# Arduino_MEGA2560_ref.net
KiCad netlist of a schematic drawn in EAGLE
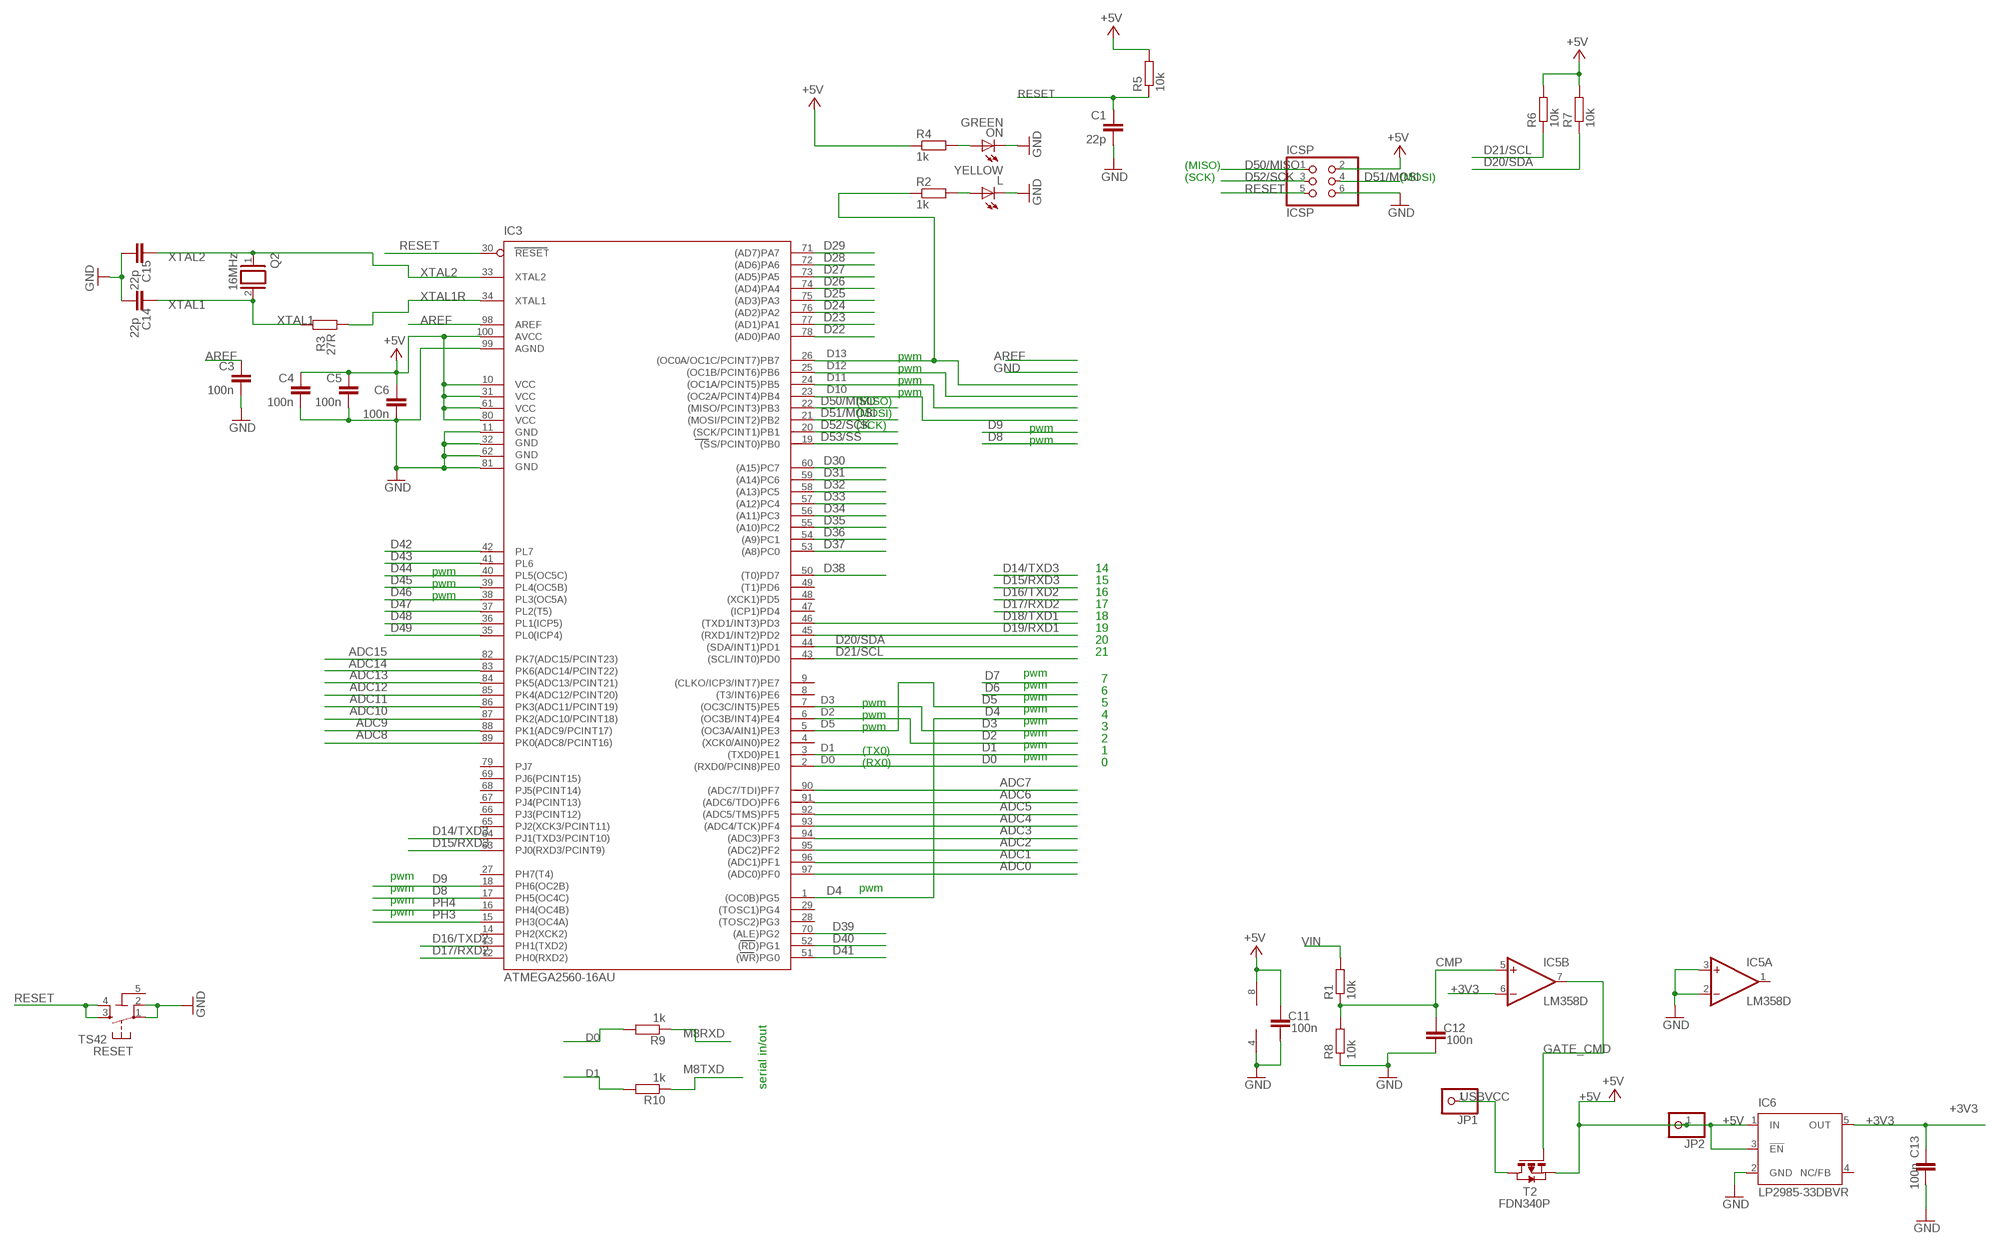
[diagram p0: schematic, sheet 1]

(export (version "E")
  (design (tool "Eeschema 10.0.6"))
  (components
    (comp (ref "C1")
      (value "22p")
      (footprint "eagle-import:C0603-ROUND")
      (libsource (lib "eagle-import") (part "C-EU0603-RND"))
    )
    (comp (ref "C3")
      (value "100n")
      (footprint "eagle-import:C0603-ROUND")
      (libsource (lib "eagle-import") (part "C-EU0603-RND"))
    )
    (comp (ref "C4")
      (value "100n")
      (footprint "eagle-import:C0603-ROUND")
      (libsource (lib "eagle-import") (part "C-EU0603-RND"))
    )
    (comp (ref "C5")
      (value "100n")
      (footprint "eagle-import:C0603-ROUND")
      (libsource (lib "eagle-import") (part "C-EU0603-RND"))
    )
    (comp (ref "C6")
      (value "100n")
      (footprint "eagle-import:C0603-ROUND")
      (libsource (lib "eagle-import") (part "C-EU0603-RND"))
    )
    (comp (ref "C11")
      (value "100n")
      (footprint "eagle-import:C0603")
      (libsource (lib "eagle-import") (part "rcl_C-EUC0603"))
    )
    (comp (ref "C12")
      (value "100n")
      (footprint "eagle-import:C0603-ROUND")
      (libsource (lib "eagle-import") (part "C-EU0603-RND"))
    )
    (comp (ref "C13")
      (value "100n")
      (footprint "eagle-import:C0603-ROUND")
      (libsource (lib "eagle-import") (part "C-EU0603-RND"))
    )
    (comp (ref "C14")
      (value "22p")
      (footprint "eagle-import:C0603-ROUND")
      (libsource (lib "eagle-import") (part "C-EU0603-RND"))
    )
    (comp (ref "C15")
      (value "22p")
      (footprint "eagle-import:C0603-ROUND")
      (libsource (lib "eagle-import") (part "C-EU0603-RND"))
    )
    (comp (ref "IC3")
      (value "ATMEGA2560-16AU")
      (footprint "eagle-import:TQFP100")
      (libsource (lib "eagle-import") (part "ATMEGAAU1280-16"))
    )
    (comp (ref "IC5")
      (value "LM358D")
      (footprint "eagle-import:SO08")
      (libsource (lib "eagle-import") (part "LM358D"))
    )
    (comp (ref "IC6")
      (value "LP2985-33DBVR")
      (footprint "eagle-import:SOT23-DBV")
      (libsource (lib "eagle-import") (part "TPS77033"))
    )
    (comp (ref "ICSP")
      (value "ICSP")
      (footprint "eagle-import:2X03")
      (libsource (lib "eagle-import") (part "PINHD-2X3"))
    )
    (comp (ref "JP1")
      (value "PINHD-1X1")
      (footprint "eagle-import:1X01")
      (libsource (lib "eagle-import") (part "PINHD-1X1"))
    )
    (comp (ref "JP2")
      (value "PINHD-1X1")
      (footprint "eagle-import:1X01")
      (libsource (lib "eagle-import") (part "PINHD-1X1"))
    )
    (comp (ref "L")
      (value "YELLOW")
      (footprint "eagle-import:CHIP-LED0805")
      (libsource (lib "eagle-import") (part "LEDCHIP-LED0805"))
    )
    (comp (ref "ON")
      (value "GREEN")
      (footprint "eagle-import:CHIP-LED0805")
      (libsource (lib "eagle-import") (part "LEDCHIP-LED0805"))
    )
    (comp (ref "Q2")
      (value "16MHz")
      (footprint "eagle-import:QS")
      (libsource (lib "eagle-import") (part "XTAL/S"))
    )
    (comp (ref "R1")
      (value "10k")
      (footprint "eagle-import:R0603")
      (libsource (lib "eagle-import") (part "rcl_334_R-EU_R0603"))
    )
    (comp (ref "R2")
      (value "1k")
      (footprint "eagle-import:R0603")
      (libsource (lib "eagle-import") (part "rcl_334_R-EU_R0603"))
    )
    (comp (ref "R3")
      (value "27R")
      (footprint "eagle-import:R0603-ROUND")
      (libsource (lib "eagle-import") (part "R-EU_R0603"))
    )
    (comp (ref "R4")
      (value "1k")
      (footprint "eagle-import:R0603")
      (libsource (lib "eagle-import") (part "rcl_334_R-EU_R0603"))
    )
    (comp (ref "R5")
      (value "10k")
      (footprint "eagle-import:R0603")
      (libsource (lib "eagle-import") (part "rcl_334_R-EU_R0603"))
    )
    (comp (ref "R6")
      (value "10k")
      (footprint "eagle-import:R0603")
      (libsource (lib "eagle-import") (part "rcl_334_R-EU_R0603"))
    )
    (comp (ref "R7")
      (value "10k")
      (footprint "eagle-import:R0603")
      (libsource (lib "eagle-import") (part "rcl_334_R-EU_R0603"))
    )
    (comp (ref "R8")
      (value "10k")
      (footprint "eagle-import:R0603")
      (libsource (lib "eagle-import") (part "rcl_334_R-EU_R0603"))
    )
    (comp (ref "R9")
      (value "1k")
      (footprint "eagle-import:R0603")
      (libsource (lib "eagle-import") (part "rcl_334_R-EU_R0603"))
    )
    (comp (ref "R10")
      (value "1k")
      (footprint "eagle-import:R0603")
      (libsource (lib "eagle-import") (part "rcl_334_R-EU_R0603"))
    )
    (comp (ref "RESET")
      (value "TS42")
      (footprint "eagle-import:TS42")
      (libsource (lib "eagle-import") (part "TS42"))
    )
    (comp (ref "T2")
      (value "FDN340P")
      (footprint "eagle-import:SOT-23")
      (libsource (lib "eagle-import") (part "PMOSSOT23"))
    )
  )
  (nets
    (net (code "1") (name "+5V") (class "Default")
      (node (ref "C11") (pin "2") (pinfunction "2_2") (pintype "passive"))
      (node (ref "C4") (pin "1") (pinfunction "1_1") (pintype "passive"))
      (node (ref "C5") (pin "1") (pinfunction "1_1") (pintype "passive"))
      (node (ref "C6") (pin "1") (pinfunction "1_1") (pintype "passive"))
      (node (ref "IC3") (pin "10") (pinfunction "VCC_10") (pintype "power_in"))
      (node (ref "IC3") (pin "100") (pinfunction "AVCC_100") (pintype "power_in"))
      (node (ref "IC3") (pin "31") (pinfunction "VCC1_31") (pintype "power_in"))
      (node (ref "IC3") (pin "61") (pinfunction "VCC2_61") (pintype "power_in"))
      (node (ref "IC3") (pin "80") (pinfunction "VCC3_80") (pintype "power_in"))
      (node (ref "IC5") (pin "8") (pinfunction "V+_8") (pintype "power_in"))
      (node (ref "IC6") (pin "1") (pinfunction "IN_1") (pintype "input"))
      (node (ref "IC6") (pin "3") (pinfunction "~{EN}_3") (pintype "input"))
      (node (ref "ICSP") (pin "2") (pinfunction "2_2") (pintype "passive"))
      (node (ref "JP2") (pin "1") (pinfunction "1_1") (pintype "passive"))
      (node (ref "R4") (pin "1") (pinfunction "1_1") (pintype "passive"))
      (node (ref "R5") (pin "2") (pinfunction "2_2") (pintype "passive"))
      (node (ref "R6") (pin "2") (pinfunction "2_2") (pintype "passive"))
      (node (ref "R7") (pin "2") (pinfunction "2_2") (pintype "passive"))
      (node (ref "T2") (pin "2") (pinfunction "S_2") (pintype "passive"))
    )
    (net (code "2") (name "/+3V3") (class "Default")
      (node (ref "C13") (pin "2") (pinfunction "2_2") (pintype "passive"))
      (node (ref "IC5") (pin "6") (pinfunction "-IN_6") (pintype "input"))
      (node (ref "IC6") (pin "5") (pinfunction "OUT_5") (pintype "passive"))
    )
    (net (code "3") (name "/5-GND") (class "Default")
      (node (ref "RESET") (pin "5") (pinfunction "5-GND_5") (pintype "power_in"))
    )
    (net (code "4") (name "/ADC0") (class "Default")
      (node (ref "IC3") (pin "97") (pinfunction "(ADC0)PF0_97") (pintype "bidirectional"))
    )
    (net (code "5") (name "/ADC1") (class "Default")
      (node (ref "IC3") (pin "96") (pinfunction "(ADC1)PF1_96") (pintype "bidirectional"))
    )
    (net (code "6") (name "/ADC2") (class "Default")
      (node (ref "IC3") (pin "95") (pinfunction "(ADC2)PF2_95") (pintype "bidirectional"))
    )
    (net (code "7") (name "/ADC3") (class "Default")
      (node (ref "IC3") (pin "94") (pinfunction "(ADC3)PF3_94") (pintype "bidirectional"))
    )
    (net (code "8") (name "/ADC4") (class "Default")
      (node (ref "IC3") (pin "93") (pinfunction "(ADC4/TCK)PF4_93") (pintype "bidirectional"))
    )
    (net (code "9") (name "/ADC5") (class "Default")
      (node (ref "IC3") (pin "92") (pinfunction "(ADC5/TMS)PF5_92") (pintype "bidirectional"))
    )
    (net (code "10") (name "/ADC6") (class "Default")
      (node (ref "IC3") (pin "91") (pinfunction "(ADC6/TDO)PF6_91") (pintype "bidirectional"))
    )
    (net (code "11") (name "/ADC7") (class "Default")
      (node (ref "IC3") (pin "90") (pinfunction "(ADC7/TDI)PF7_90") (pintype "bidirectional"))
    )
    (net (code "12") (name "/ADC8") (class "Default")
      (node (ref "IC3") (pin "89") (pinfunction "PK0(ADC8/PCINT16)_89") (pintype "bidirectional"))
    )
    (net (code "13") (name "/ADC9") (class "Default")
      (node (ref "IC3") (pin "88") (pinfunction "PK1(ADC9/PCINT17)_88") (pintype "bidirectional"))
    )
    (net (code "14") (name "/ADC10") (class "Default")
      (node (ref "IC3") (pin "87") (pinfunction "PK2(ADC10/PCINT18)_87") (pintype "bidirectional"))
    )
    (net (code "15") (name "/ADC11") (class "Default")
      (node (ref "IC3") (pin "86") (pinfunction "PK3(ADC11/PCINT19)_86") (pintype "bidirectional"))
    )
    (net (code "16") (name "/ADC12") (class "Default")
      (node (ref "IC3") (pin "85") (pinfunction "PK4(ADC12/PCINT20)_85") (pintype "bidirectional"))
    )
    (net (code "17") (name "/ADC13") (class "Default")
      (node (ref "IC3") (pin "84") (pinfunction "PK5(ADC13/PCINT21)_84") (pintype "bidirectional"))
    )
    (net (code "18") (name "/ADC14") (class "Default")
      (node (ref "IC3") (pin "83") (pinfunction "PK6(ADC14/PCINT22)_83") (pintype "bidirectional"))
    )
    (net (code "19") (name "/ADC15") (class "Default")
      (node (ref "IC3") (pin "82") (pinfunction "PK7(ADC15/PCINT23)_82") (pintype "bidirectional"))
    )
    (net (code "20") (name "/AREF") (class "Default")
      (node (ref "C3") (pin "1") (pinfunction "1_1") (pintype "passive"))
      (node (ref "IC3") (pin "98") (pinfunction "AREF_98") (pintype "bidirectional"))
    )
    (net (code "21") (name "/CMP") (class "Default")
      (node (ref "C12") (pin "2") (pinfunction "2_2") (pintype "passive"))
      (node (ref "IC5") (pin "5") (pinfunction "+IN_5") (pintype "input"))
      (node (ref "R1") (pin "1") (pinfunction "1_1") (pintype "passive"))
      (node (ref "R8") (pin "2") (pinfunction "2_2") (pintype "passive"))
    )
    (net (code "22") (name "/D0") (class "Default")
      (node (ref "IC3") (pin "2") (pinfunction "(RXD0/PCIN8)PE0_2") (pintype "bidirectional"))
      (node (ref "R9") (pin "2") (pinfunction "2_2") (pintype "passive"))
    )
    (net (code "23") (name "/D1") (class "Default")
      (node (ref "IC3") (pin "3") (pinfunction "(TXD0)PE1_3") (pintype "bidirectional"))
      (node (ref "R10") (pin "2") (pinfunction "2_2") (pintype "passive"))
    )
    (net (code "24") (name "/D2") (class "Default")
      (node (ref "IC3") (pin "6") (pinfunction "(OC3B/INT4)PE4_6") (pintype "bidirectional"))
    )
    (net (code "25") (name "/D3") (class "Default")
      (node (ref "IC3") (pin "7") (pinfunction "(OC3C/INT5)PE5_7") (pintype "bidirectional"))
    )
    (net (code "26") (name "/D4") (class "Default")
      (node (ref "IC3") (pin "1") (pinfunction "(OC0B)PG5_1") (pintype "bidirectional"))
    )
    (net (code "27") (name "/D5") (class "Default")
      (node (ref "IC3") (pin "5") (pinfunction "(OC3A/AIN1)PE3_5") (pintype "bidirectional"))
    )
    (net (code "30") (name "/D8") (class "Default")
      (node (ref "IC3") (pin "17") (pinfunction "PH5(OC4C)_17") (pintype "bidirectional"))
    )
    (net (code "31") (name "/D9") (class "Default")
      (node (ref "IC3") (pin "18") (pinfunction "PH6(OC2B)_18") (pintype "bidirectional"))
    )
    (net (code "32") (name "/D10") (class "Default")
      (node (ref "IC3") (pin "23") (pinfunction "(OC2A/PCINT4)PB4_23") (pintype "bidirectional"))
    )
    (net (code "33") (name "/D11") (class "Default")
      (node (ref "IC3") (pin "24") (pinfunction "(OC1A/PCINT5)PB5_24") (pintype "bidirectional"))
    )
    (net (code "34") (name "/D12") (class "Default")
      (node (ref "IC3") (pin "25") (pinfunction "(OC1B/PCINT6)PB6_25") (pintype "bidirectional"))
    )
    (net (code "35") (name "/D13") (class "Default")
      (node (ref "IC3") (pin "26") (pinfunction "(OC0A/OC1C/PCINT7)PB7_26") (pintype "bidirectional"))
      (node (ref "R2") (pin "1") (pinfunction "1_1") (pintype "passive"))
    )
    (net (code "36") (name "/D14{slash}TXD3") (class "Default")
      (node (ref "IC3") (pin "64") (pinfunction "PJ1(TXD3/PCINT10)_64") (pintype "bidirectional"))
    )
    (net (code "37") (name "/D15{slash}RXD3") (class "Default")
      (node (ref "IC3") (pin "63") (pinfunction "PJ0(RXD3/PCINT9)_63") (pintype "bidirectional"))
    )
    (net (code "38") (name "/D16{slash}TXD2") (class "Default")
      (node (ref "IC3") (pin "13") (pinfunction "PH1(TXD2)_13") (pintype "bidirectional"))
    )
    (net (code "39") (name "/D17{slash}RXD2") (class "Default")
      (node (ref "IC3") (pin "12") (pinfunction "PH0(RXD2)_12") (pintype "bidirectional"))
    )
    (net (code "40") (name "/D18{slash}TXD1") (class "Default")
      (node (ref "IC3") (pin "46") (pinfunction "(TXD1/INT3)PD3_46") (pintype "bidirectional"))
    )
    (net (code "41") (name "/D19{slash}RXD1") (class "Default")
      (node (ref "IC3") (pin "45") (pinfunction "(RXD1/INT2)PD2_45") (pintype "bidirectional"))
    )
    (net (code "42") (name "/D20{slash}SDA") (class "Default")
      (node (ref "IC3") (pin "44") (pinfunction "(SDA/INT1)PD1_44") (pintype "bidirectional"))
      (node (ref "R7") (pin "1") (pinfunction "1_1") (pintype "passive"))
    )
    (net (code "43") (name "/D21{slash}SCL") (class "Default")
      (node (ref "IC3") (pin "43") (pinfunction "(SCL/INT0)PD0_43") (pintype "bidirectional"))
      (node (ref "R6") (pin "1") (pinfunction "1_1") (pintype "passive"))
    )
    (net (code "44") (name "/D22") (class "Default")
      (node (ref "IC3") (pin "78") (pinfunction "(AD0)PA0_78") (pintype "bidirectional"))
    )
    (net (code "45") (name "/D23") (class "Default")
      (node (ref "IC3") (pin "77") (pinfunction "(AD1)PA1_77") (pintype "bidirectional"))
    )
    (net (code "46") (name "/D24") (class "Default")
      (node (ref "IC3") (pin "76") (pinfunction "(AD2)PA2_76") (pintype "bidirectional"))
    )
    (net (code "47") (name "/D25") (class "Default")
      (node (ref "IC3") (pin "75") (pinfunction "(AD3)PA3_75") (pintype "bidirectional"))
    )
    (net (code "48") (name "/D26") (class "Default")
      (node (ref "IC3") (pin "74") (pinfunction "(AD4)PA4_74") (pintype "bidirectional"))
    )
    (net (code "49") (name "/D27") (class "Default")
      (node (ref "IC3") (pin "73") (pinfunction "(AD5)PA5_73") (pintype "bidirectional"))
    )
    (net (code "50") (name "/D28") (class "Default")
      (node (ref "IC3") (pin "72") (pinfunction "(AD6)PA6_72") (pintype "bidirectional"))
    )
    (net (code "51") (name "/D29") (class "Default")
      (node (ref "IC3") (pin "71") (pinfunction "(AD7)PA7_71") (pintype "bidirectional"))
    )
    (net (code "52") (name "/D30") (class "Default")
      (node (ref "IC3") (pin "60") (pinfunction "(A15)PC7_60") (pintype "bidirectional"))
    )
    (net (code "53") (name "/D31") (class "Default")
      (node (ref "IC3") (pin "59") (pinfunction "(A14)PC6_59") (pintype "bidirectional"))
    )
    (net (code "54") (name "/D32") (class "Default")
      (node (ref "IC3") (pin "58") (pinfunction "(A13)PC5_58") (pintype "bidirectional"))
    )
    (net (code "55") (name "/D33") (class "Default")
      (node (ref "IC3") (pin "57") (pinfunction "(A12)PC4_57") (pintype "bidirectional"))
    )
    (net (code "56") (name "/D34") (class "Default")
      (node (ref "IC3") (pin "56") (pinfunction "(A11)PC3_56") (pintype "bidirectional"))
    )
    (net (code "57") (name "/D35") (class "Default")
      (node (ref "IC3") (pin "55") (pinfunction "(A10)PC2_55") (pintype "bidirectional"))
    )
    (net (code "58") (name "/D36") (class "Default")
      (node (ref "IC3") (pin "54") (pinfunction "(A9)PC1_54") (pintype "bidirectional"))
    )
    (net (code "59") (name "/D37") (class "Default")
      (node (ref "IC3") (pin "53") (pinfunction "(A8)PC0_53") (pintype "bidirectional"))
    )
    (net (code "60") (name "/D38") (class "Default")
      (node (ref "IC3") (pin "50") (pinfunction "(T0)PD7_50") (pintype "bidirectional"))
    )
    (net (code "61") (name "/D39") (class "Default")
      (node (ref "IC3") (pin "70") (pinfunction "(ALE)PG2_70") (pintype "bidirectional"))
    )
    (net (code "62") (name "/D40") (class "Default")
      (node (ref "IC3") (pin "52") (pinfunction "(RD)PG1_52") (pintype "bidirectional"))
    )
    (net (code "63") (name "/D41") (class "Default")
      (node (ref "IC3") (pin "51") (pinfunction "(WR)PG0_51") (pintype "bidirectional"))
    )
    (net (code "64") (name "/D42") (class "Default")
      (node (ref "IC3") (pin "42") (pinfunction "PL7_42") (pintype "bidirectional"))
    )
    (net (code "65") (name "/D43") (class "Default")
      (node (ref "IC3") (pin "41") (pinfunction "PL6_41") (pintype "bidirectional"))
    )
    (net (code "66") (name "/D44") (class "Default")
      (node (ref "IC3") (pin "40") (pinfunction "PL5(OC5C)_40") (pintype "bidirectional"))
    )
    (net (code "67") (name "/D45") (class "Default")
      (node (ref "IC3") (pin "39") (pinfunction "PL4(OC5B)_39") (pintype "bidirectional"))
    )
    (net (code "68") (name "/D46") (class "Default")
      (node (ref "IC3") (pin "38") (pinfunction "PL3(OC5A)_38") (pintype "bidirectional"))
    )
    (net (code "69") (name "/D47") (class "Default")
      (node (ref "IC3") (pin "37") (pinfunction "PL2(T5)_37") (pintype "bidirectional"))
    )
    (net (code "70") (name "/D48") (class "Default")
      (node (ref "IC3") (pin "36") (pinfunction "PL1(ICP5)_36") (pintype "bidirectional"))
    )
    (net (code "71") (name "/D49") (class "Default")
      (node (ref "IC3") (pin "35") (pinfunction "PL0(ICP4)_35") (pintype "bidirectional"))
    )
    (net (code "72") (name "/D50{slash}MISO") (class "Default")
      (node (ref "IC3") (pin "22") (pinfunction "(MISO/PCINT3)PB3_22") (pintype "bidirectional"))
      (node (ref "ICSP") (pin "1") (pinfunction "1_1") (pintype "passive"))
    )
    (net (code "73") (name "/D51{slash}MOSI") (class "Default")
      (node (ref "IC3") (pin "21") (pinfunction "(MOSI/PCINT2)PB2_21") (pintype "bidirectional"))
      (node (ref "ICSP") (pin "4") (pinfunction "4_4") (pintype "passive"))
    )
    (net (code "74") (name "/D52{slash}SCK") (class "Default")
      (node (ref "IC3") (pin "20") (pinfunction "(SCK/PCINT1)PB1_20") (pintype "bidirectional"))
      (node (ref "ICSP") (pin "3") (pinfunction "3_3") (pintype "passive"))
    )
    (net (code "75") (name "/D53{slash}SS") (class "Default")
      (node (ref "IC3") (pin "19") (pinfunction "(SS/PCINT0)PB0_19") (pintype "bidirectional"))
    )
    (net (code "76") (name "/GATE_CMD") (class "Default")
      (node (ref "IC5") (pin "7") (pinfunction "OUT_7") (pintype "output"))
      (node (ref "T2") (pin "3") (pinfunction "G_3") (pintype "passive"))
    )
    (net (code "77") (name "/M8RXD") (class "Default")
      (node (ref "R9") (pin "1") (pinfunction "1_1") (pintype "passive"))
    )
    (net (code "78") (name "/M8TXD") (class "Default")
      (node (ref "R10") (pin "1") (pinfunction "1_1") (pintype "passive"))
    )
    (net (code "79") (name "/PH3") (class "Default")
      (node (ref "IC3") (pin "15") (pinfunction "PH3(OC4A)_15") (pintype "bidirectional"))
    )
    (net (code "80") (name "/PH4") (class "Default")
      (node (ref "IC3") (pin "16") (pinfunction "PH4(OC4B)_16") (pintype "bidirectional"))
    )
    (net (code "81") (name "/RESET") (class "Default")
      (node (ref "C1") (pin "1") (pinfunction "1_1") (pintype "passive"))
      (node (ref "IC3") (pin "30") (pinfunction "RESET_30") (pintype "input"))
      (node (ref "ICSP") (pin "5") (pinfunction "5_5") (pintype "passive"))
      (node (ref "R5") (pin "1") (pinfunction "1_1") (pintype "passive"))
      (node (ref "RESET") (pin "3") (pinfunction "3_3") (pintype "passive"))
      (node (ref "RESET") (pin "4") (pinfunction "4_4") (pintype "passive"))
    )
    (net (code "82") (name "/USBVCC") (class "Default")
      (node (ref "JP1") (pin "1") (pinfunction "1_1") (pintype "passive"))
      (node (ref "T2") (pin "1") (pinfunction "D_1") (pintype "passive"))
    )
    (net (code "83") (name "/VIN") (class "Default")
      (node (ref "R1") (pin "2") (pinfunction "2_2") (pintype "passive"))
    )
    (net (code "84") (name "/XTAL1") (class "Default")
      (node (ref "C14") (pin "2") (pinfunction "2_2") (pintype "passive"))
      (node (ref "Q2") (pin "2") (pinfunction "2_2") (pintype "passive"))
      (node (ref "R3") (pin "2") (pinfunction "2_2") (pintype "passive"))
    )
    (net (code "85") (name "/XTAL1R") (class "Default")
      (node (ref "IC3") (pin "34") (pinfunction "XTAL1_34") (pintype "input"))
      (node (ref "R3") (pin "1") (pinfunction "1_1") (pintype "passive"))
    )
    (net (code "86") (name "/XTAL2") (class "Default")
      (node (ref "C15") (pin "2") (pinfunction "2_2") (pintype "passive"))
      (node (ref "IC3") (pin "33") (pinfunction "XTAL2_33") (pintype "output"))
      (node (ref "Q2") (pin "1") (pinfunction "1_1") (pintype "passive"))
    )
    (net (code "87") (name "GND") (class "Default")
      (node (ref "C1") (pin "2") (pinfunction "2_2") (pintype "passive"))
      (node (ref "C11") (pin "1") (pinfunction "1_1") (pintype "passive"))
      (node (ref "C12") (pin "1") (pinfunction "1_1") (pintype "passive"))
      (node (ref "C13") (pin "1") (pinfunction "1_1") (pintype "passive"))
      (node (ref "C14") (pin "1") (pinfunction "1_1") (pintype "passive"))
      (node (ref "C15") (pin "1") (pinfunction "1_1") (pintype "passive"))
      (node (ref "C3") (pin "2") (pinfunction "2_2") (pintype "passive"))
      (node (ref "C4") (pin "2") (pinfunction "2_2") (pintype "passive"))
      (node (ref "C5") (pin "2") (pinfunction "2_2") (pintype "passive"))
      (node (ref "C6") (pin "2") (pinfunction "2_2") (pintype "passive"))
      (node (ref "IC3") (pin "11") (pinfunction "GND_11") (pintype "power_in"))
      (node (ref "IC3") (pin "32") (pinfunction "GND1_32") (pintype "power_in"))
      (node (ref "IC3") (pin "62") (pinfunction "GND2_62") (pintype "power_in"))
      (node (ref "IC3") (pin "81") (pinfunction "GND3_81") (pintype "power_in"))
      (node (ref "IC3") (pin "99") (pinfunction "AGND_99") (pintype "power_in"))
      (node (ref "IC5") (pin "2") (pinfunction "-IN_2") (pintype "input"))
      (node (ref "IC5") (pin "3") (pinfunction "+IN_3") (pintype "input"))
      (node (ref "IC5") (pin "4") (pinfunction "V-_4") (pintype "power_in"))
      (node (ref "IC6") (pin "2") (pinfunction "GND_2") (pintype "power_in"))
      (node (ref "ICSP") (pin "6") (pinfunction "6_6") (pintype "passive"))
      (node (ref "L") (pin "C") (pinfunction "C_C") (pintype "passive"))
      (node (ref "ON") (pin "C") (pinfunction "C_C") (pintype "passive"))
      (node (ref "R8") (pin "1") (pinfunction "1_1") (pintype "passive"))
      (node (ref "RESET") (pin "1") (pinfunction "1_1") (pintype "passive"))
      (node (ref "RESET") (pin "2") (pinfunction "2_2") (pintype "passive"))
    )
    (net (code "88") (name "Net-(L-PadA)") (class "Default")
      (node (ref "L") (pin "A") (pinfunction "A_A") (pintype "passive"))
      (node (ref "R2") (pin "2") (pinfunction "2_2") (pintype "passive"))
    )
    (net (code "89") (name "Net-(ON-PadA)") (class "Default")
      (node (ref "ON") (pin "A") (pinfunction "A_A") (pintype "passive"))
      (node (ref "R4") (pin "2") (pinfunction "2_2") (pintype "passive"))
    )
    (net (code "90") (name "unconnected-(IC3-(CLKO{slash}ICP3{slash}INT7)PE7-Pad9)") (class "Default")
      (node (ref "IC3") (pin "9") (pinfunction "(CLKO/ICP3/INT7)PE7_9") (pintype "bidirectional"))
    )
    (net (code "91") (name "unconnected-(IC3-(ICP1)PD4-Pad47)") (class "Default")
      (node (ref "IC3") (pin "47") (pinfunction "(ICP1)PD4_47") (pintype "bidirectional"))
    )
    (net (code "92") (name "unconnected-(IC3-(T1)PD6-Pad49)") (class "Default")
      (node (ref "IC3") (pin "49") (pinfunction "(T1)PD6_49") (pintype "bidirectional"))
    )
    (net (code "93") (name "unconnected-(IC3-(T3{slash}INT6)PE6-Pad8)") (class "Default")
      (node (ref "IC3") (pin "8") (pinfunction "(T3/INT6)PE6_8") (pintype "bidirectional"))
    )
    (net (code "94") (name "unconnected-(IC3-(TOSC1)PG4-Pad29)") (class "Default")
      (node (ref "IC3") (pin "29") (pinfunction "(TOSC1)PG4_29") (pintype "bidirectional"))
    )
    (net (code "95") (name "unconnected-(IC3-(TOSC2)PG3-Pad28)") (class "Default")
      (node (ref "IC3") (pin "28") (pinfunction "(TOSC2)PG3_28") (pintype "bidirectional"))
    )
    (net (code "96") (name "unconnected-(IC3-(XCK0{slash}AIN0)PE2-Pad4)") (class "Default")
      (node (ref "IC3") (pin "4") (pinfunction "(XCK0/AIN0)PE2_4") (pintype "bidirectional"))
    )
    (net (code "97") (name "unconnected-(IC3-(XCK1)PD5-Pad48)") (class "Default")
      (node (ref "IC3") (pin "48") (pinfunction "(XCK1)PD5_48") (pintype "bidirectional"))
    )
    (net (code "98") (name "unconnected-(IC3-PH2(XCK2)-Pad14)") (class "Default")
      (node (ref "IC3") (pin "14") (pinfunction "PH2(XCK2)_14") (pintype "bidirectional"))
    )
    (net (code "99") (name "unconnected-(IC3-PH7(T4)-Pad27)") (class "Default")
      (node (ref "IC3") (pin "27") (pinfunction "PH7(T4)_27") (pintype "bidirectional"))
    )
    (net (code "100") (name "unconnected-(IC3-PJ2(XCK3{slash}PCINT11)-Pad65)") (class "Default")
      (node (ref "IC3") (pin "65") (pinfunction "PJ2(XCK3/PCINT11)_65") (pintype "bidirectional"))
    )
    (net (code "101") (name "unconnected-(IC3-PJ3(PCINT12)-Pad66)") (class "Default")
      (node (ref "IC3") (pin "66") (pinfunction "PJ3(PCINT12)_66") (pintype "bidirectional"))
    )
    (net (code "102") (name "unconnected-(IC3-PJ4(PCINT13)-Pad67)") (class "Default")
      (node (ref "IC3") (pin "67") (pinfunction "PJ4(PCINT13)_67") (pintype "bidirectional"))
    )
    (net (code "103") (name "unconnected-(IC3-PJ5(PCINT14)-Pad68)") (class "Default")
      (node (ref "IC3") (pin "68") (pinfunction "PJ5(PCINT14)_68") (pintype "bidirectional"))
    )
    (net (code "104") (name "unconnected-(IC3-PJ6(PCINT15)-Pad69)") (class "Default")
      (node (ref "IC3") (pin "69") (pinfunction "PJ6(PCINT15)_69") (pintype "bidirectional"))
    )
    (net (code "105") (name "unconnected-(IC3-PJ7-Pad79)") (class "Default")
      (node (ref "IC3") (pin "79") (pinfunction "PJ7_79") (pintype "bidirectional"))
    )
    (net (code "106") (name "unconnected-(IC5A-OUT-Pad1)") (class "Default")
      (node (ref "IC5") (pin "1") (pinfunction "OUT_1") (pintype "output"))
    )
    (net (code "107") (name "unconnected-(IC6-NC{slash}FB-Pad4)") (class "Default")
      (node (ref "IC6") (pin "4") (pinfunction "NC/FB_4") (pintype "passive"))
    )
  )
)
